# Schematic-16pin.net
KiCad netlist of a schematic drawn in Altium Designer
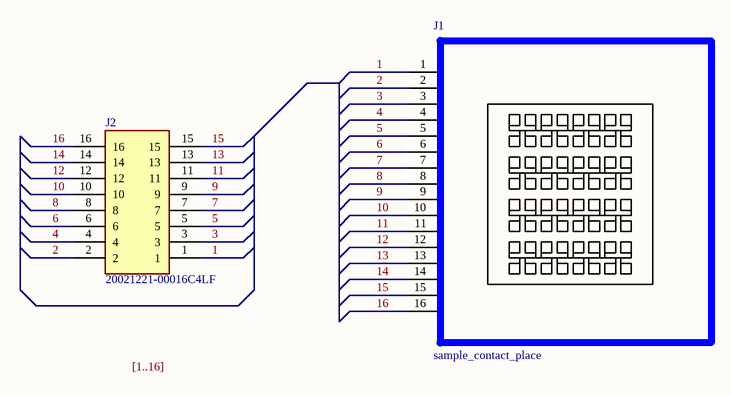
[diagram p0: Schematic-16pin.SchDoc]

(export (version "E")
  (design (tool "Eeschema 10.0.6"))
  (components
    (comp (ref "J1")
      (value "sample_contact_place")
      (footprint "sample")
      (libsource (lib "sample_holder_library") (part "sample_contact_place"))
    )
    (comp (ref "J2")
      (value "20021221-00016C4LF")
      (footprint "2002122100016C4LF")
      (description "Connector")
      (libsource (lib "sample_holder_library") (part "20021221-00016C4LF"))
    )
  )
  (nets
    (net (code "1") (name "/1") (class "Default")
      (node (ref "J1") (pin "1") (pinfunction "1_1") (pintype "passive"))
      (node (ref "J2") (pin "1") (pinfunction "1_1") (pintype "passive"))
    )
    (net (code "2") (name "/2") (class "Default")
      (node (ref "J1") (pin "2") (pinfunction "2_2") (pintype "passive"))
      (node (ref "J2") (pin "2") (pinfunction "2_2") (pintype "passive"))
    )
    (net (code "3") (name "/3") (class "Default")
      (node (ref "J1") (pin "3") (pinfunction "3_3") (pintype "passive"))
      (node (ref "J2") (pin "3") (pinfunction "3_3") (pintype "passive"))
    )
    (net (code "4") (name "/4") (class "Default")
      (node (ref "J1") (pin "4") (pinfunction "4_4") (pintype "passive"))
      (node (ref "J2") (pin "4") (pinfunction "4_4") (pintype "passive"))
    )
    (net (code "5") (name "/5") (class "Default")
      (node (ref "J1") (pin "5") (pinfunction "5_5") (pintype "passive"))
      (node (ref "J2") (pin "5") (pinfunction "5_5") (pintype "passive"))
    )
    (net (code "6") (name "/6") (class "Default")
      (node (ref "J1") (pin "6") (pinfunction "6_6") (pintype "passive"))
      (node (ref "J2") (pin "6") (pinfunction "6_6") (pintype "passive"))
    )
    (net (code "7") (name "/7") (class "Default")
      (node (ref "J1") (pin "7") (pinfunction "7_7") (pintype "passive"))
      (node (ref "J2") (pin "7") (pinfunction "7_7") (pintype "passive"))
    )
    (net (code "8") (name "/8") (class "Default")
      (node (ref "J1") (pin "8") (pinfunction "8_8") (pintype "passive"))
      (node (ref "J2") (pin "8") (pinfunction "8_8") (pintype "passive"))
    )
    (net (code "9") (name "/9") (class "Default")
      (node (ref "J1") (pin "9") (pinfunction "9_9") (pintype "passive"))
      (node (ref "J2") (pin "9") (pinfunction "9_9") (pintype "passive"))
    )
    (net (code "10") (name "/10") (class "Default")
      (node (ref "J1") (pin "10") (pinfunction "10_10") (pintype "passive"))
      (node (ref "J2") (pin "10") (pinfunction "10_10") (pintype "passive"))
    )
    (net (code "11") (name "/11") (class "Default")
      (node (ref "J1") (pin "11") (pinfunction "11_11") (pintype "passive"))
      (node (ref "J2") (pin "11") (pinfunction "11_11") (pintype "passive"))
    )
    (net (code "12") (name "/12") (class "Default")
      (node (ref "J1") (pin "12") (pinfunction "12_12") (pintype "passive"))
      (node (ref "J2") (pin "12") (pinfunction "12_12") (pintype "passive"))
    )
    (net (code "13") (name "/13") (class "Default")
      (node (ref "J1") (pin "13") (pinfunction "13_13") (pintype "passive"))
      (node (ref "J2") (pin "13") (pinfunction "13_13") (pintype "passive"))
    )
    (net (code "14") (name "/14") (class "Default")
      (node (ref "J1") (pin "14") (pinfunction "14_14") (pintype "passive"))
      (node (ref "J2") (pin "14") (pinfunction "14_14") (pintype "passive"))
    )
    (net (code "15") (name "/15") (class "Default")
      (node (ref "J1") (pin "15") (pinfunction "15_15") (pintype "passive"))
      (node (ref "J2") (pin "15") (pinfunction "15_15") (pintype "passive"))
    )
    (net (code "16") (name "/16") (class "Default")
      (node (ref "J1") (pin "16") (pinfunction "16_16") (pintype "passive"))
      (node (ref "J2") (pin "16") (pinfunction "16_16") (pintype "passive"))
    )
  )
)
